# Sheet1.net
KiCad netlist of a schematic drawn in Altium Designer
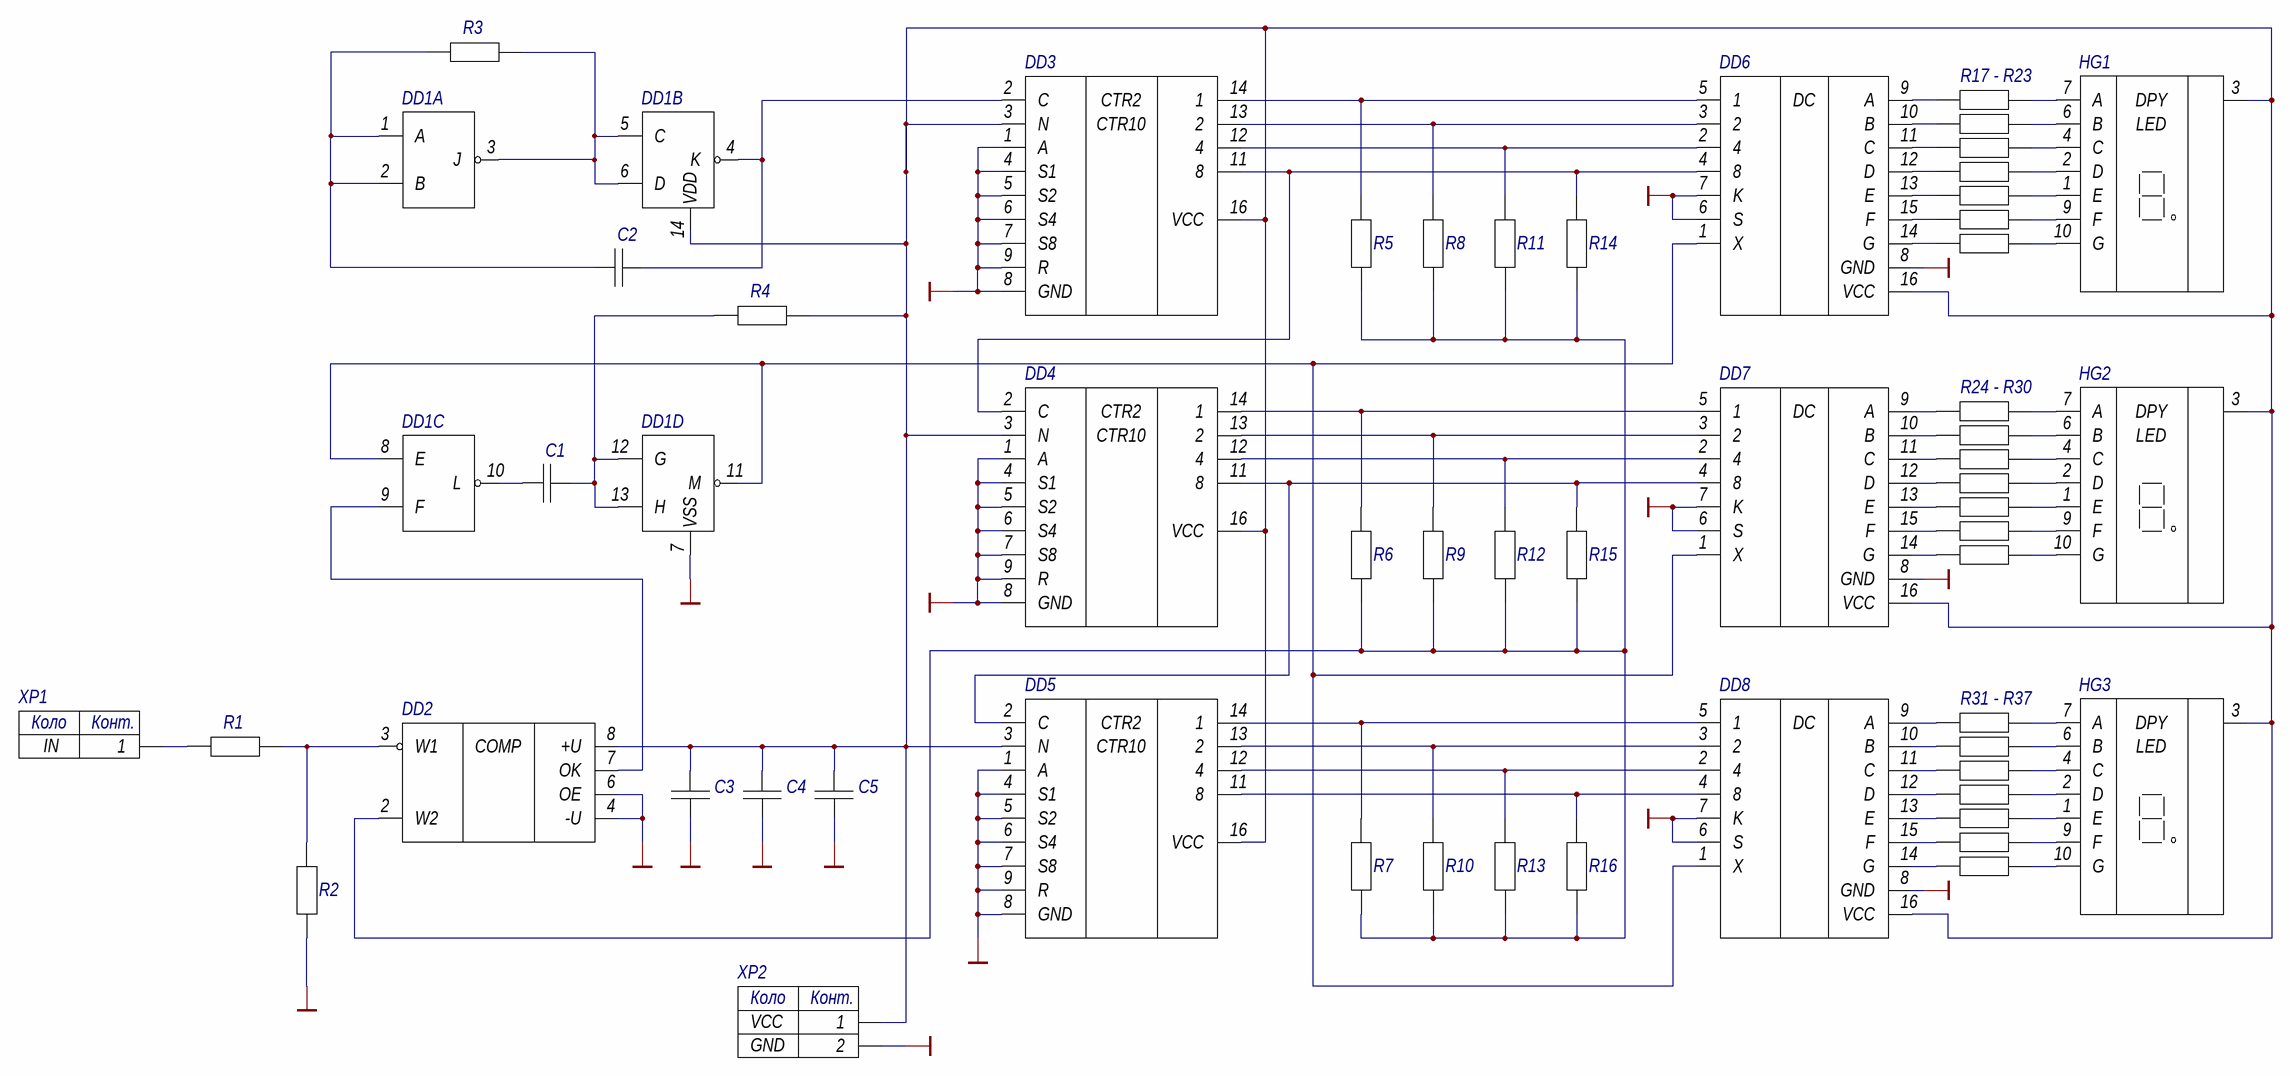
[diagram p0: Sheet1.SchDoc]

(export (version "E")
  (design (tool "Eeschema 10.0.6"))
  (components
    (comp (ref "C1")
      (value "C-0805 50 В 1,2 нФ 10% X7R KEMET")
      (footprint "CAPC2012X09N")
      (description "CAP CER 1200PF 50V X7R 0805")
      (fields (field (name "VOLTAGE") "50 В") (field (name "MANUFACTURER") "KEMET"))
      (libsource (lib "Schlib1") (part "C0805C122K5RAC7800"))
    )
    (comp (ref "C2")
      (value "C-0805 50 В 1,8 нФ 10% X7R KEMET")
      (footprint "CAPC2012X09N")
      (description "CAP CER 1800PF 50V X7R 0805")
      (fields (field (name "VOLTAGE") "50 В") (field (name "MANUFACTURER") "KEMET"))
      (libsource (lib "Schlib1") (part "C0805C182K5RAC7800"))
    )
    (comp (ref "C3")
      (value "C-1210 16 В 100 мкФ 20% X5R KEMET")
      (footprint "CAPC3225X27N")
      (description "CAP CER 100UF 16V X5R 1210")
      (fields (field (name "VOLTAGE") "16 В") (field (name "MANUFACTURER") "KEMET"))
      (libsource (lib "Schlib1") (part "C1210C107M4PAC7800"))
    )
    (comp (ref "C4")
      (value "C-1210 16 В 100 мкФ 20% X5R KEMET")
      (footprint "CAPC3225X27N")
      (description "CAP CER 100UF 16V X5R 1210")
      (fields (field (name "VOLTAGE") "16 В") (field (name "MANUFACTURER") "KEMET"))
      (libsource (lib "Schlib1") (part "C1210C107M4PAC7800"))
    )
    (comp (ref "C5")
      (value "C-1210 16 В 100 мкФ 20% X5R KEMET")
      (footprint "CAPC3225X27N")
      (description "CAP CER 100UF 16V X5R 1210")
      (fields (field (name "VOLTAGE") "16 В") (field (name "MANUFACTURER") "KEMET"))
      (libsource (lib "Schlib1") (part "C1210C107M4PAC7800"))
    )
    (comp (ref "DD1")
      (value "CD4001BPWR Texas Instruments")
      (footprint "TSOP65P640X120-14N")
      (description "IC GATE NOR 4CH 2-INP 14TSSOP")
      (fields (field (name "MANUFACTURER") "Texas Instruments"))
      (libsource (lib "Schlib1") (part "CD4001BPWR"))
    )
    (comp (ref "DD2")
      (value "LM311N STMicroelectronics")
      (footprint "DIP-8_STM")
      (description "IC VOLTAGE COMPARATOR 8-DIP")
      (fields (field (name "MANUFACTURER") "STMicroelectronics"))
      (libsource (lib "Schlib1") (part "LM311N"))
    )
    (comp (ref "DD3")
      (value "TC-5971")
      (footprint "TC5971")
      (description "IC COUNTER BINARY/DECADE")
      (libsource (lib "Schlib1") (part "TC-5971"))
    )
    (comp (ref "DD4")
      (value "TC-5971")
      (footprint "TC5971")
      (description "IC COUNTER BINARY/DECADE")
      (libsource (lib "Schlib1") (part "TC-5971"))
    )
    (comp (ref "DD5")
      (value "TC-5971")
      (footprint "TC5971")
      (description "IC COUNTER BINARY/DECADE")
      (libsource (lib "Schlib1") (part "TC-5971"))
    )
    (comp (ref "DD6")
      (value "CD4511BNSR Texas Instruments")
      (footprint "SOIC127P780X200-16N")
      (description "IC DRVR 7 SEGMENT 16SO")
      (fields (field (name "MANUFACTURER") "Texas Instruments"))
      (libsource (lib "Schlib1") (part "CD4511BNSR"))
    )
    (comp (ref "DD7")
      (value "CD4511BNSR Texas Instruments")
      (footprint "SOIC127P780X200-16N")
      (description "IC DRVR 7 SEGMENT 16SO")
      (fields (field (name "MANUFACTURER") "Texas Instruments"))
      (libsource (lib "Schlib1") (part "CD4511BNSR"))
    )
    (comp (ref "DD8")
      (value "CD4511BNSR Texas Instruments")
      (footprint "SOIC127P780X200-16N")
      (description "IC DRVR 7 SEGMENT 16SO")
      (fields (field (name "MANUFACTURER") "Texas Instruments"))
      (libsource (lib "Schlib1") (part "CD4511BNSR"))
    )
    (comp (ref "HG1")
      (value "ACSC56-41QBWA/D-F01 Kingbright")
      (footprint "ACSX56-41")
      (description "DISPLAY 7SEG 0.56\" SGL BLU 10SMD")
      (fields (field (name "MANUFACTURER") "Kingbright"))
      (libsource (lib "Schlib1") (part "ACSC56-41QBWA/D-F01"))
    )
    (comp (ref "HG2")
      (value "ACSC56-41QBWA/D-F01 Kingbright")
      (footprint "ACSX56-41")
      (description "DISPLAY 7SEG 0.56\" SGL BLU 10SMD")
      (fields (field (name "MANUFACTURER") "Kingbright"))
      (libsource (lib "Schlib1") (part "ACSC56-41QBWA/D-F01"))
    )
    (comp (ref "HG3")
      (value "ACSC56-41QBWA/D-F01 Kingbright")
      (footprint "ACSX56-41")
      (description "DISPLAY 7SEG 0.56\" SGL BLU 10SMD")
      (fields (field (name "MANUFACTURER") "Kingbright"))
      (libsource (lib "Schlib1") (part "ACSC56-41QBWA/D-F01"))
    )
    (comp (ref "R1")
      (value "R-0805 0,125 Вт 10 кОм 5% YAGEO")
      (footprint "RESC2012X05N")
      (description "RES 10K OHM 5% 1/8W 0805")
      (fields (field (name "POWER") "0,125 Вт") (field (name "TOLERANCE") "5%"))
      (libsource (lib "Schlib1") (part "RC0805JR-0710KL"))
    )
    (comp (ref "R2")
      (value "R-0805 0,125 Вт 100 кОм 5% YAGEO")
      (footprint "RESC2012X05N")
      (description "RES 100K OHM 5% 1/8W 0805")
      (fields (field (name "POWER") "0,125 Вт") (field (name "TOLERANCE") "5%"))
      (libsource (lib "Schlib1") (part "RC0805JR-07100KL"))
    )
    (comp (ref "R3")
      (value "R-0805 0,125 Вт 360 кОм 5% YAGEO")
      (footprint "RESC2012X05N")
      (description "RES 360K OHM 5% 1/8W 0805")
      (fields (field (name "POWER") "0,125 Вт") (field (name "TOLERANCE") "5%"))
      (libsource (lib "Schlib1") (part "RC0805JR-07360KL"))
    )
    (comp (ref "R4")
      (value "R-0805 0,125 Вт 360 кОм 5% YAGEO")
      (footprint "RESC2012X05N")
      (description "RES 360K OHM 5% 1/8W 0805")
      (fields (field (name "POWER") "0,125 Вт") (field (name "TOLERANCE") "5%"))
      (libsource (lib "Schlib1") (part "RC0805JR-07360KL"))
    )
    (comp (ref "R5")
      (value "R-0805 0,125 Вт 36 кОм 5% YAGEO")
      (footprint "RESC2012X05N")
      (description "RES 36K OHM 5% 1/8W 0805")
      (fields (field (name "POWER") "0,125 Вт") (field (name "TOLERANCE") "5%"))
      (libsource (lib "Schlib1") (part "RC0805JR-0736KL"))
    )
    (comp (ref "R6")
      (value "R-0805 0,125 Вт 360 кОм 5% YAGEO")
      (footprint "RESC2012X05N")
      (description "RES 360K OHM 5% 1/8W 0805")
      (fields (field (name "POWER") "0,125 Вт") (field (name "TOLERANCE") "5%"))
      (libsource (lib "Schlib1") (part "RC0805JR-07360KL"))
    )
    (comp (ref "R7")
      (value "R-0805 0,125 Вт 3,6 МОм 5% YAGEO")
      (footprint "RESC2012X05N")
      (description "RES 3.6M OHM 5% 1/8W 0805")
      (fields (field (name "POWER") "0,125 Вт") (field (name "TOLERANCE") "5%"))
      (libsource (lib "Schlib1") (part "RC0805JR-073M6L"))
    )
    (comp (ref "R8")
      (value "R-0805 0,125 Вт 18 кОм 5% YAGEO")
      (footprint "RESC2012X05N")
      (description "RES 18K OHM 5% 1/8W 0805")
      (fields (field (name "POWER") "0,125 Вт") (field (name "TOLERANCE") "5%"))
      (libsource (lib "Schlib1") (part "RC0805JR-0718KL"))
    )
    (comp (ref "R9")
      (value "R-0805 0,125 Вт 180 кОм 5% YAGEO")
      (footprint "RESC2012X05N")
      (description "RES 180K OHM 5% 1/8W 0805")
      (fields (field (name "POWER") "0,125 Вт") (field (name "TOLERANCE") "5%"))
      (libsource (lib "Schlib1") (part "RC0805JR-07180KL"))
    )
    (comp (ref "R10")
      (value "R-0805 0,125 Вт 1,8 МОм 5% YAGEO")
      (footprint "RESC2012X05N")
      (description "RES 1.8M OHM 5% 1/8W 0805")
      (fields (field (name "POWER") "0,125 Вт") (field (name "TOLERANCE") "5%"))
      (libsource (lib "Schlib1") (part "RC0805JR-071M8L"))
    )
    (comp (ref "R11")
      (value "R-0805 0,125 Вт 9,1 кОм 5% YAGEO")
      (footprint "RESC2012X05N")
      (description "RES 9.1K OHM 5% 1/8W 0805")
      (fields (field (name "POWER") "0,125 Вт") (field (name "TOLERANCE") "5%"))
      (libsource (lib "Schlib1") (part "RC0805JR-079K1L"))
    )
    (comp (ref "R12")
      (value "R-0805 0,125 Вт 91 кОм 5% YAGEO")
      (footprint "RESC2012X05N")
      (description "RES 91K OHM 5% 1/8W 0805")
      (fields (field (name "POWER") "0,125 Вт") (field (name "TOLERANCE") "5%"))
      (libsource (lib "Schlib1") (part "RC0805JR-0791KL"))
    )
    (comp (ref "R13")
      (value "R-0805 0,125 Вт 910 кОм 5% YAGEO")
      (footprint "RESC2012X05N")
      (description "RES 910K OHM 5% 1/8W 0805")
      (fields (field (name "POWER") "0,125 Вт") (field (name "TOLERANCE") "5%"))
      (libsource (lib "Schlib1") (part "RC0805JR-07910KL"))
    )
    (comp (ref "R14")
      (value "R-0805 0,125 Вт 4,7 кОм 5% YAGEO")
      (footprint "RESC2012X05N")
      (description "RES 4.7K OHM 5% 1/8W 0805")
      (fields (field (name "POWER") "0,125 Вт") (field (name "TOLERANCE") "5%"))
      (libsource (lib "Schlib1") (part "RC0805JR-074K7L"))
    )
    (comp (ref "R15")
      (value "R-0805 0,125 Вт 47 кОм 5% YAGEO")
      (footprint "RESC2012X05N")
      (description "RES 47K OHM 5% 1/8W 0805")
      (fields (field (name "POWER") "0,125 Вт") (field (name "TOLERANCE") "5%"))
      (libsource (lib "Schlib1") (part "RC0805JR-0747KL"))
    )
    (comp (ref "R16")
      (value "R-0805 0,125 Вт 470 кОм 5% YAGEO")
      (footprint "RESC2012X05N")
      (description "RES 470K OHM 5% 1/8W 0805")
      (fields (field (name "POWER") "0,125 Вт") (field (name "TOLERANCE") "5%"))
      (libsource (lib "Schlib1") (part "RC0805JR-07470KL"))
    )
    (comp (ref "R17")
      (value "R-0805 0,125 Вт 470 кОм 5% YAGEO")
      (footprint "RESC2012X05N")
      (description "RES 470K OHM 5% 1/8W 0805")
      (fields (field (name "POWER") "0,125 Вт") (field (name "TOLERANCE") "5%"))
      (libsource (lib "Schlib1") (part "RC0805JR-07470KL"))
    )
    (comp (ref "R18")
      (value "R-0805 0,125 Вт 470 кОм 5% YAGEO")
      (footprint "RESC2012X05N")
      (description "RES 470K OHM 5% 1/8W 0805")
      (fields (field (name "POWER") "0,125 Вт") (field (name "TOLERANCE") "5%"))
      (libsource (lib "Schlib1") (part "RC0805JR-07470KL"))
    )
    (comp (ref "R19")
      (value "R-0805 0,125 Вт 470 кОм 5% YAGEO")
      (footprint "RESC2012X05N")
      (description "RES 470K OHM 5% 1/8W 0805")
      (fields (field (name "POWER") "0,125 Вт") (field (name "TOLERANCE") "5%"))
      (libsource (lib "Schlib1") (part "RC0805JR-07470KL"))
    )
    (comp (ref "R20")
      (value "R-0805 0,125 Вт 470 кОм 5% YAGEO")
      (footprint "RESC2012X05N")
      (description "RES 470K OHM 5% 1/8W 0805")
      (fields (field (name "POWER") "0,125 Вт") (field (name "TOLERANCE") "5%"))
      (libsource (lib "Schlib1") (part "RC0805JR-07470KL"))
    )
    (comp (ref "R21")
      (value "R-0805 0,125 Вт 470 кОм 5% YAGEO")
      (footprint "RESC2012X05N")
      (description "RES 470K OHM 5% 1/8W 0805")
      (fields (field (name "POWER") "0,125 Вт") (field (name "TOLERANCE") "5%"))
      (libsource (lib "Schlib1") (part "RC0805JR-07470KL"))
    )
    (comp (ref "R22")
      (value "R-0805 0,125 Вт 470 кОм 5% YAGEO")
      (footprint "RESC2012X05N")
      (description "RES 470K OHM 5% 1/8W 0805")
      (fields (field (name "POWER") "0,125 Вт") (field (name "TOLERANCE") "5%"))
      (libsource (lib "Schlib1") (part "RC0805JR-07470KL"))
    )
    (comp (ref "R23")
      (value "R-0805 0,125 Вт 470 кОм 5% YAGEO")
      (footprint "RESC2012X05N")
      (description "RES 470K OHM 5% 1/8W 0805")
      (fields (field (name "POWER") "0,125 Вт") (field (name "TOLERANCE") "5%"))
      (libsource (lib "Schlib1") (part "RC0805JR-07470KL"))
    )
    (comp (ref "R24")
      (value "R-0805 0,125 Вт 470 кОм 5% YAGEO")
      (footprint "RESC2012X05N")
      (description "RES 470K OHM 5% 1/8W 0805")
      (fields (field (name "POWER") "0,125 Вт") (field (name "TOLERANCE") "5%"))
      (libsource (lib "Schlib1") (part "RC0805JR-07470KL"))
    )
    (comp (ref "R25")
      (value "R-0805 0,125 Вт 470 кОм 5% YAGEO")
      (footprint "RESC2012X05N")
      (description "RES 470K OHM 5% 1/8W 0805")
      (fields (field (name "POWER") "0,125 Вт") (field (name "TOLERANCE") "5%"))
      (libsource (lib "Schlib1") (part "RC0805JR-07470KL"))
    )
    (comp (ref "R26")
      (value "R-0805 0,125 Вт 470 кОм 5% YAGEO")
      (footprint "RESC2012X05N")
      (description "RES 470K OHM 5% 1/8W 0805")
      (fields (field (name "POWER") "0,125 Вт") (field (name "TOLERANCE") "5%"))
      (libsource (lib "Schlib1") (part "RC0805JR-07470KL"))
    )
    (comp (ref "R27")
      (value "R-0805 0,125 Вт 470 кОм 5% YAGEO")
      (footprint "RESC2012X05N")
      (description "RES 470K OHM 5% 1/8W 0805")
      (fields (field (name "POWER") "0,125 Вт") (field (name "TOLERANCE") "5%"))
      (libsource (lib "Schlib1") (part "RC0805JR-07470KL"))
    )
    (comp (ref "R28")
      (value "R-0805 0,125 Вт 470 кОм 5% YAGEO")
      (footprint "RESC2012X05N")
      (description "RES 470K OHM 5% 1/8W 0805")
      (fields (field (name "POWER") "0,125 Вт") (field (name "TOLERANCE") "5%"))
      (libsource (lib "Schlib1") (part "RC0805JR-07470KL"))
    )
    (comp (ref "R29")
      (value "R-0805 0,125 Вт 470 кОм 5% YAGEO")
      (footprint "RESC2012X05N")
      (description "RES 470K OHM 5% 1/8W 0805")
      (fields (field (name "POWER") "0,125 Вт") (field (name "TOLERANCE") "5%"))
      (libsource (lib "Schlib1") (part "RC0805JR-07470KL"))
    )
    (comp (ref "R30")
      (value "R-0805 0,125 Вт 470 кОм 5% YAGEO")
      (footprint "RESC2012X05N")
      (description "RES 470K OHM 5% 1/8W 0805")
      (fields (field (name "POWER") "0,125 Вт") (field (name "TOLERANCE") "5%"))
      (libsource (lib "Schlib1") (part "RC0805JR-07470KL"))
    )
    (comp (ref "R31")
      (value "R-0805 0,125 Вт 470 кОм 5% YAGEO")
      (footprint "RESC2012X05N")
      (description "RES 470K OHM 5% 1/8W 0805")
      (fields (field (name "POWER") "0,125 Вт") (field (name "TOLERANCE") "5%"))
      (libsource (lib "Schlib1") (part "RC0805JR-07470KL"))
    )
    (comp (ref "R32")
      (value "R-0805 0,125 Вт 470 кОм 5% YAGEO")
      (footprint "RESC2012X05N")
      (description "RES 470K OHM 5% 1/8W 0805")
      (fields (field (name "POWER") "0,125 Вт") (field (name "TOLERANCE") "5%"))
      (libsource (lib "Schlib1") (part "RC0805JR-07470KL"))
    )
    (comp (ref "R33")
      (value "R-0805 0,125 Вт 470 кОм 5% YAGEO")
      (footprint "RESC2012X05N")
      (description "RES 470K OHM 5% 1/8W 0805")
      (fields (field (name "POWER") "0,125 Вт") (field (name "TOLERANCE") "5%"))
      (libsource (lib "Schlib1") (part "RC0805JR-07470KL"))
    )
    (comp (ref "R34")
      (value "R-0805 0,125 Вт 470 кОм 5% YAGEO")
      (footprint "RESC2012X05N")
      (description "RES 470K OHM 5% 1/8W 0805")
      (fields (field (name "POWER") "0,125 Вт") (field (name "TOLERANCE") "5%"))
      (libsource (lib "Schlib1") (part "RC0805JR-07470KL"))
    )
    (comp (ref "R35")
      (value "R-0805 0,125 Вт 470 кОм 5% YAGEO")
      (footprint "RESC2012X05N")
      (description "RES 470K OHM 5% 1/8W 0805")
      (fields (field (name "POWER") "0,125 Вт") (field (name "TOLERANCE") "5%"))
      (libsource (lib "Schlib1") (part "RC0805JR-07470KL"))
    )
    (comp (ref "R36")
      (value "R-0805 0,125 Вт 470 кОм 5% YAGEO")
      (footprint "RESC2012X05N")
      (description "RES 470K OHM 5% 1/8W 0805")
      (fields (field (name "POWER") "0,125 Вт") (field (name "TOLERANCE") "5%"))
      (libsource (lib "Schlib1") (part "RC0805JR-07470KL"))
    )
    (comp (ref "R37")
      (value "R-0805 0,125 Вт 470 кОм 5% YAGEO")
      (footprint "RESC2012X05N")
      (description "RES 470K OHM 5% 1/8W 0805")
      (fields (field (name "POWER") "0,125 Вт") (field (name "TOLERANCE") "5%"))
      (libsource (lib "Schlib1") (part "RC0805JR-07470KL"))
    )
    (comp (ref "XP1")
      (value "61300111121 Würth Elektronik")
      (footprint "PLS-1")
      (description "CONN HEADER VERT 1POS")
      (fields (field (name "MANUFACTURER") "Würth Elektronik"))
      (libsource (lib "Schlib1") (part "61300111121"))
    )
    (comp (ref "XP2")
      (value "61300211121 Würth Elektronik")
      (footprint "PLS-2")
      (description "CONN HEADER VERT 2POS 2.54MM")
      (fields (field (name "MANUFACTURER") "Würth Elektronik"))
      (libsource (lib "Schlib1") (part "61300211121"))
    )
  )
  (nets
    (net (code "1") (name "GND") (class "Default")
      (node (ref "C3") (pin "1") (pinfunction "1_1") (pintype "passive"))
      (node (ref "C4") (pin "1") (pinfunction "1_1") (pintype "passive"))
      (node (ref "C5") (pin "1") (pinfunction "1_1") (pintype "passive"))
      (node (ref "DD1") (pin "7") (pinfunction "VSS_7") (pintype "passive"))
      (node (ref "DD2") (pin "4") (pinfunction "-U_4") (pintype "passive"))
      (node (ref "DD2") (pin "6") (pinfunction "OE_6") (pintype "passive"))
      (node (ref "DD3") (pin "1") (pinfunction "A_1") (pintype "passive"))
      (node (ref "DD3") (pin "4") (pinfunction "S1_4") (pintype "passive"))
      (node (ref "DD3") (pin "5") (pinfunction "S2_5") (pintype "passive"))
      (node (ref "DD3") (pin "6") (pinfunction "S4_6") (pintype "passive"))
      (node (ref "DD3") (pin "7") (pinfunction "S8_7") (pintype "passive"))
      (node (ref "DD3") (pin "8") (pinfunction "GND_8") (pintype "passive"))
      (node (ref "DD3") (pin "9") (pinfunction "R_9") (pintype "passive"))
      (node (ref "DD4") (pin "1") (pinfunction "A_1") (pintype "passive"))
      (node (ref "DD4") (pin "4") (pinfunction "S1_4") (pintype "passive"))
      (node (ref "DD4") (pin "5") (pinfunction "S2_5") (pintype "passive"))
      (node (ref "DD4") (pin "6") (pinfunction "S4_6") (pintype "passive"))
      (node (ref "DD4") (pin "7") (pinfunction "S8_7") (pintype "passive"))
      (node (ref "DD4") (pin "8") (pinfunction "GND_8") (pintype "passive"))
      (node (ref "DD4") (pin "9") (pinfunction "R_9") (pintype "passive"))
      (node (ref "DD5") (pin "1") (pinfunction "A_1") (pintype "passive"))
      (node (ref "DD5") (pin "4") (pinfunction "S1_4") (pintype "passive"))
      (node (ref "DD5") (pin "5") (pinfunction "S2_5") (pintype "passive"))
      (node (ref "DD5") (pin "6") (pinfunction "S4_6") (pintype "passive"))
      (node (ref "DD5") (pin "7") (pinfunction "S8_7") (pintype "passive"))
      (node (ref "DD5") (pin "8") (pinfunction "GND_8") (pintype "passive"))
      (node (ref "DD5") (pin "9") (pinfunction "R_9") (pintype "passive"))
      (node (ref "DD6") (pin "6") (pinfunction "S_6") (pintype "passive"))
      (node (ref "DD6") (pin "7") (pinfunction "K_7") (pintype "passive"))
      (node (ref "DD6") (pin "8") (pinfunction "GND_8") (pintype "passive"))
      (node (ref "DD7") (pin "6") (pinfunction "S_6") (pintype "passive"))
      (node (ref "DD7") (pin "7") (pinfunction "K_7") (pintype "passive"))
      (node (ref "DD7") (pin "8") (pinfunction "GND_8") (pintype "passive"))
      (node (ref "DD8") (pin "6") (pinfunction "S_6") (pintype "passive"))
      (node (ref "DD8") (pin "7") (pinfunction "K_7") (pintype "passive"))
      (node (ref "DD8") (pin "8") (pinfunction "GND_8") (pintype "passive"))
      (node (ref "R2") (pin "1") (pinfunction "1_1") (pintype "passive"))
      (node (ref "XP2") (pin "2") (pinfunction "2_2") (pintype "passive"))
    )
    (net (code "2") (name "Net-(DD1A-A)") (class "Default")
      (node (ref "C2") (pin "1") (pinfunction "1_1") (pintype "passive"))
      (node (ref "DD1") (pin "1") (pinfunction "A_1") (pintype "passive"))
      (node (ref "DD1") (pin "2") (pinfunction "B_2") (pintype "passive"))
      (node (ref "R3") (pin "1") (pinfunction "1_1") (pintype "passive"))
    )
    (net (code "3") (name "Net-(DD1A-J)") (class "Default")
      (node (ref "DD1") (pin "3") (pinfunction "J_3") (pintype "passive"))
      (node (ref "DD1") (pin "5") (pinfunction "C_5") (pintype "passive"))
      (node (ref "DD1") (pin "6") (pinfunction "D_6") (pintype "passive"))
      (node (ref "R3") (pin "2") (pinfunction "2_2") (pintype "passive"))
    )
    (net (code "4") (name "Net-(DD1B-K)") (class "Default")
      (node (ref "C2") (pin "2") (pinfunction "2_2") (pintype "passive"))
      (node (ref "DD1") (pin "4") (pinfunction "K_4") (pintype "passive"))
      (node (ref "DD3") (pin "2") (pinfunction "C_2") (pintype "passive"))
    )
    (net (code "5") (name "Net-(DD1B-VDD)") (class "Default")
      (node (ref "C3") (pin "2") (pinfunction "2_2") (pintype "passive"))
      (node (ref "C4") (pin "2") (pinfunction "2_2") (pintype "passive"))
      (node (ref "C5") (pin "2") (pinfunction "2_2") (pintype "passive"))
      (node (ref "DD1") (pin "14") (pinfunction "VDD_14") (pintype "passive"))
      (node (ref "DD2") (pin "8") (pinfunction "+U_8") (pintype "passive"))
      (node (ref "DD3") (pin "16") (pinfunction "VCC_16") (pintype "passive"))
      (node (ref "DD3") (pin "3") (pinfunction "N_3") (pintype "passive"))
      (node (ref "DD4") (pin "16") (pinfunction "VCC_16") (pintype "passive"))
      (node (ref "DD4") (pin "3") (pinfunction "N_3") (pintype "passive"))
      (node (ref "DD5") (pin "16") (pinfunction "VCC_16") (pintype "passive"))
      (node (ref "DD5") (pin "3") (pinfunction "N_3") (pintype "passive"))
      (node (ref "DD6") (pin "16") (pinfunction "VCC_16") (pintype "passive"))
      (node (ref "DD7") (pin "16") (pinfunction "VCC_16") (pintype "passive"))
      (node (ref "DD8") (pin "16") (pinfunction "VCC_16") (pintype "passive"))
      (node (ref "HG1") (pin "3") (pinfunction "3_3") (pintype "passive"))
      (node (ref "HG2") (pin "3") (pinfunction "3_3") (pintype "passive"))
      (node (ref "HG3") (pin "3") (pinfunction "3_3") (pintype "passive"))
      (node (ref "R4") (pin "2") (pinfunction "2_2") (pintype "passive"))
      (node (ref "XP2") (pin "1") (pinfunction "1_1") (pintype "passive"))
    )
    (net (code "6") (name "Net-(DD1C-E)") (class "Default")
      (node (ref "DD1") (pin "11") (pinfunction "M_11") (pintype "passive"))
      (node (ref "DD1") (pin "8") (pinfunction "E_8") (pintype "passive"))
      (node (ref "DD6") (pin "1") (pinfunction "X_1") (pintype "passive"))
      (node (ref "DD7") (pin "1") (pinfunction "X_1") (pintype "passive"))
      (node (ref "DD8") (pin "1") (pinfunction "X_1") (pintype "passive"))
    )
    (net (code "7") (name "Net-(DD1C-F)") (class "Default")
      (node (ref "DD1") (pin "9") (pinfunction "F_9") (pintype "passive"))
      (node (ref "DD2") (pin "7") (pinfunction "OK_7") (pintype "passive"))
    )
    (net (code "8") (name "Net-(DD1C-L)") (class "Default")
      (node (ref "C1") (pin "1") (pinfunction "1_1") (pintype "passive"))
      (node (ref "DD1") (pin "10") (pinfunction "L_10") (pintype "passive"))
    )
    (net (code "9") (name "Net-(DD1D-G)") (class "Default")
      (node (ref "C1") (pin "2") (pinfunction "2_2") (pintype "passive"))
      (node (ref "DD1") (pin "12") (pinfunction "G_12") (pintype "passive"))
      (node (ref "DD1") (pin "13") (pinfunction "H_13") (pintype "passive"))
      (node (ref "R4") (pin "1") (pinfunction "1_1") (pintype "passive"))
    )
    (net (code "10") (name "Net-(DD2-W1)") (class "Default")
      (node (ref "DD2") (pin "3") (pinfunction "W1_3") (pintype "passive"))
      (node (ref "R1") (pin "2") (pinfunction "2_2") (pintype "passive"))
      (node (ref "R2") (pin "2") (pinfunction "2_2") (pintype "passive"))
    )
    (net (code "11") (name "Net-(DD2-W2)") (class "Default")
      (node (ref "DD2") (pin "2") (pinfunction "W2_2") (pintype "passive"))
      (node (ref "R10") (pin "1") (pinfunction "1_1") (pintype "passive"))
      (node (ref "R11") (pin "1") (pinfunction "1_1") (pintype "passive"))
      (node (ref "R12") (pin "1") (pinfunction "1_1") (pintype "passive"))
      (node (ref "R13") (pin "1") (pinfunction "1_1") (pintype "passive"))
      (node (ref "R14") (pin "1") (pinfunction "1_1") (pintype "passive"))
      (node (ref "R15") (pin "1") (pinfunction "1_1") (pintype "passive"))
      (node (ref "R16") (pin "1") (pinfunction "1_1") (pintype "passive"))
      (node (ref "R5") (pin "1") (pinfunction "1_1") (pintype "passive"))
      (node (ref "R6") (pin "1") (pinfunction "1_1") (pintype "passive"))
      (node (ref "R7") (pin "1") (pinfunction "1_1") (pintype "passive"))
      (node (ref "R8") (pin "1") (pinfunction "1_1") (pintype "passive"))
      (node (ref "R9") (pin "1") (pinfunction "1_1") (pintype "passive"))
    )
    (net (code "12") (name "Net-(DD3-1)") (class "Default")
      (node (ref "DD3") (pin "14") (pinfunction "1_14") (pintype "passive"))
      (node (ref "DD6") (pin "5") (pinfunction "1_5") (pintype "passive"))
      (node (ref "R5") (pin "2") (pinfunction "2_2") (pintype "passive"))
    )
    (net (code "13") (name "Net-(DD3-2)") (class "Default")
      (node (ref "DD3") (pin "13") (pinfunction "2_13") (pintype "passive"))
      (node (ref "DD6") (pin "3") (pinfunction "2_3") (pintype "passive"))
      (node (ref "R8") (pin "2") (pinfunction "2_2") (pintype "passive"))
    )
    (net (code "14") (name "Net-(DD3-4)") (class "Default")
      (node (ref "DD3") (pin "12") (pinfunction "4_12") (pintype "passive"))
      (node (ref "DD6") (pin "2") (pinfunction "4_2") (pintype "passive"))
      (node (ref "R11") (pin "2") (pinfunction "2_2") (pintype "passive"))
    )
    (net (code "15") (name "Net-(DD3-8)") (class "Default")
      (node (ref "DD3") (pin "11") (pinfunction "8_11") (pintype "passive"))
      (node (ref "DD4") (pin "2") (pinfunction "C_2") (pintype "passive"))
      (node (ref "DD6") (pin "4") (pinfunction "8_4") (pintype "passive"))
      (node (ref "R14") (pin "2") (pinfunction "2_2") (pintype "passive"))
    )
    (net (code "16") (name "Net-(DD4-1)") (class "Default")
      (node (ref "DD4") (pin "14") (pinfunction "1_14") (pintype "passive"))
      (node (ref "DD7") (pin "5") (pinfunction "1_5") (pintype "passive"))
      (node (ref "R6") (pin "2") (pinfunction "2_2") (pintype "passive"))
    )
    (net (code "17") (name "Net-(DD4-2)") (class "Default")
      (node (ref "DD4") (pin "13") (pinfunction "2_13") (pintype "passive"))
      (node (ref "DD7") (pin "3") (pinfunction "2_3") (pintype "passive"))
      (node (ref "R9") (pin "2") (pinfunction "2_2") (pintype "passive"))
    )
    (net (code "18") (name "Net-(DD4-4)") (class "Default")
      (node (ref "DD4") (pin "12") (pinfunction "4_12") (pintype "passive"))
      (node (ref "DD7") (pin "2") (pinfunction "4_2") (pintype "passive"))
      (node (ref "R12") (pin "2") (pinfunction "2_2") (pintype "passive"))
    )
    (net (code "19") (name "Net-(DD4-8)") (class "Default")
      (node (ref "DD4") (pin "11") (pinfunction "8_11") (pintype "passive"))
      (node (ref "DD5") (pin "2") (pinfunction "C_2") (pintype "passive"))
      (node (ref "DD7") (pin "4") (pinfunction "8_4") (pintype "passive"))
      (node (ref "R15") (pin "2") (pinfunction "2_2") (pintype "passive"))
    )
    (net (code "20") (name "Net-(DD5-1)") (class "Default")
      (node (ref "DD5") (pin "14") (pinfunction "1_14") (pintype "passive"))
      (node (ref "DD8") (pin "5") (pinfunction "1_5") (pintype "passive"))
      (node (ref "R7") (pin "2") (pinfunction "2_2") (pintype "passive"))
    )
    (net (code "21") (name "Net-(DD5-2)") (class "Default")
      (node (ref "DD5") (pin "13") (pinfunction "2_13") (pintype "passive"))
      (node (ref "DD8") (pin "3") (pinfunction "2_3") (pintype "passive"))
      (node (ref "R10") (pin "2") (pinfunction "2_2") (pintype "passive"))
    )
    (net (code "22") (name "Net-(DD5-4)") (class "Default")
      (node (ref "DD5") (pin "12") (pinfunction "4_12") (pintype "passive"))
      (node (ref "DD8") (pin "2") (pinfunction "4_2") (pintype "passive"))
      (node (ref "R13") (pin "2") (pinfunction "2_2") (pintype "passive"))
    )
    (net (code "23") (name "Net-(DD5-8)") (class "Default")
      (node (ref "DD5") (pin "11") (pinfunction "8_11") (pintype "passive"))
      (node (ref "DD8") (pin "4") (pinfunction "8_4") (pintype "passive"))
      (node (ref "R16") (pin "2") (pinfunction "2_2") (pintype "passive"))
    )
    (net (code "24") (name "Net-(DD6-A)") (class "Default")
      (node (ref "DD6") (pin "9") (pinfunction "A_9") (pintype "passive"))
      (node (ref "R17") (pin "1") (pinfunction "1_1") (pintype "passive"))
    )
    (net (code "25") (name "Net-(DD6-B)") (class "Default")
      (node (ref "DD6") (pin "10") (pinfunction "B_10") (pintype "passive"))
      (node (ref "R18") (pin "1") (pinfunction "1_1") (pintype "passive"))
    )
    (net (code "26") (name "Net-(DD6-C)") (class "Default")
      (node (ref "DD6") (pin "11") (pinfunction "C_11") (pintype "passive"))
      (node (ref "R19") (pin "1") (pinfunction "1_1") (pintype "passive"))
    )
    (net (code "27") (name "Net-(DD6-D)") (class "Default")
      (node (ref "DD6") (pin "12") (pinfunction "D_12") (pintype "passive"))
      (node (ref "R20") (pin "1") (pinfunction "1_1") (pintype "passive"))
    )
    (net (code "28") (name "Net-(DD6-E)") (class "Default")
      (node (ref "DD6") (pin "13") (pinfunction "E_13") (pintype "passive"))
      (node (ref "R21") (pin "1") (pinfunction "1_1") (pintype "passive"))
    )
    (net (code "29") (name "Net-(DD6-F)") (class "Default")
      (node (ref "DD6") (pin "15") (pinfunction "F_15") (pintype "passive"))
      (node (ref "R22") (pin "1") (pinfunction "1_1") (pintype "passive"))
    )
    (net (code "30") (name "Net-(DD6-G)") (class "Default")
      (node (ref "DD6") (pin "14") (pinfunction "G_14") (pintype "passive"))
      (node (ref "R23") (pin "1") (pinfunction "1_1") (pintype "passive"))
    )
    (net (code "31") (name "Net-(DD7-A)") (class "Default")
      (node (ref "DD7") (pin "9") (pinfunction "A_9") (pintype "passive"))
      (node (ref "R24") (pin "1") (pinfunction "1_1") (pintype "passive"))
    )
    (net (code "32") (name "Net-(DD7-B)") (class "Default")
      (node (ref "DD7") (pin "10") (pinfunction "B_10") (pintype "passive"))
      (node (ref "R25") (pin "1") (pinfunction "1_1") (pintype "passive"))
    )
    (net (code "33") (name "Net-(DD7-C)") (class "Default")
      (node (ref "DD7") (pin "11") (pinfunction "C_11") (pintype "passive"))
      (node (ref "R26") (pin "1") (pinfunction "1_1") (pintype "passive"))
    )
    (net (code "34") (name "Net-(DD7-D)") (class "Default")
      (node (ref "DD7") (pin "12") (pinfunction "D_12") (pintype "passive"))
      (node (ref "R27") (pin "1") (pinfunction "1_1") (pintype "passive"))
    )
    (net (code "35") (name "Net-(DD7-E)") (class "Default")
      (node (ref "DD7") (pin "13") (pinfunction "E_13") (pintype "passive"))
      (node (ref "R28") (pin "1") (pinfunction "1_1") (pintype "passive"))
    )
    (net (code "36") (name "Net-(DD7-F)") (class "Default")
      (node (ref "DD7") (pin "15") (pinfunction "F_15") (pintype "passive"))
      (node (ref "R29") (pin "1") (pinfunction "1_1") (pintype "passive"))
    )
    (net (code "37") (name "Net-(DD7-G)") (class "Default")
      (node (ref "DD7") (pin "14") (pinfunction "G_14") (pintype "passive"))
      (node (ref "R30") (pin "1") (pinfunction "1_1") (pintype "passive"))
    )
    (net (code "38") (name "Net-(DD8-A)") (class "Default")
      (node (ref "DD8") (pin "9") (pinfunction "A_9") (pintype "passive"))
      (node (ref "R31") (pin "1") (pinfunction "1_1") (pintype "passive"))
    )
    (net (code "39") (name "Net-(DD8-B)") (class "Default")
      (node (ref "DD8") (pin "10") (pinfunction "B_10") (pintype "passive"))
      (node (ref "R32") (pin "1") (pinfunction "1_1") (pintype "passive"))
    )
    (net (code "40") (name "Net-(DD8-C)") (class "Default")
      (node (ref "DD8") (pin "11") (pinfunction "C_11") (pintype "passive"))
      (node (ref "R33") (pin "1") (pinfunction "1_1") (pintype "passive"))
    )
    (net (code "41") (name "Net-(DD8-D)") (class "Default")
      (node (ref "DD8") (pin "12") (pinfunction "D_12") (pintype "passive"))
      (node (ref "R34") (pin "1") (pinfunction "1_1") (pintype "passive"))
    )
    (net (code "42") (name "Net-(DD8-E)") (class "Default")
      (node (ref "DD8") (pin "13") (pinfunction "E_13") (pintype "passive"))
      (node (ref "R35") (pin "1") (pinfunction "1_1") (pintype "passive"))
    )
    (net (code "43") (name "Net-(DD8-F)") (class "Default")
      (node (ref "DD8") (pin "15") (pinfunction "F_15") (pintype "passive"))
      (node (ref "R36") (pin "1") (pinfunction "1_1") (pintype "passive"))
    )
    (net (code "44") (name "Net-(DD8-G)") (class "Default")
      (node (ref "DD8") (pin "14") (pinfunction "G_14") (pintype "passive"))
      (node (ref "R37") (pin "1") (pinfunction "1_1") (pintype "passive"))
    )
    (net (code "45") (name "Net-(HG1-A)") (class "Default")
      (node (ref "HG1") (pin "7") (pinfunction "A_7") (pintype "passive"))
      (node (ref "R17") (pin "2") (pinfunction "2_2") (pintype "passive"))
    )
    (net (code "46") (name "Net-(HG1-B)") (class "Default")
      (node (ref "HG1") (pin "6") (pinfunction "B_6") (pintype "passive"))
      (node (ref "R18") (pin "2") (pinfunction "2_2") (pintype "passive"))
    )
    (net (code "47") (name "Net-(HG1-C)") (class "Default")
      (node (ref "HG1") (pin "4") (pinfunction "C_4") (pintype "passive"))
      (node (ref "R19") (pin "2") (pinfunction "2_2") (pintype "passive"))
    )
    (net (code "48") (name "Net-(HG1-D)") (class "Default")
      (node (ref "HG1") (pin "2") (pinfunction "D_2") (pintype "passive"))
      (node (ref "R20") (pin "2") (pinfunction "2_2") (pintype "passive"))
    )
    (net (code "49") (name "Net-(HG1-E)") (class "Default")
      (node (ref "HG1") (pin "1") (pinfunction "E_1") (pintype "passive"))
      (node (ref "R21") (pin "2") (pinfunction "2_2") (pintype "passive"))
    )
    (net (code "50") (name "Net-(HG1-F)") (class "Default")
      (node (ref "HG1") (pin "9") (pinfunction "F_9") (pintype "passive"))
      (node (ref "R22") (pin "2") (pinfunction "2_2") (pintype "passive"))
    )
    (net (code "51") (name "Net-(HG1-G)") (class "Default")
      (node (ref "HG1") (pin "10") (pinfunction "G_10") (pintype "passive"))
      (node (ref "R23") (pin "2") (pinfunction "2_2") (pintype "passive"))
    )
    (net (code "52") (name "Net-(HG2-A)") (class "Default")
      (node (ref "HG2") (pin "7") (pinfunction "A_7") (pintype "passive"))
      (node (ref "R24") (pin "2") (pinfunction "2_2") (pintype "passive"))
    )
    (net (code "53") (name "Net-(HG2-B)") (class "Default")
      (node (ref "HG2") (pin "6") (pinfunction "B_6") (pintype "passive"))
      (node (ref "R25") (pin "2") (pinfunction "2_2") (pintype "passive"))
    )
    (net (code "54") (name "Net-(HG2-C)") (class "Default")
      (node (ref "HG2") (pin "4") (pinfunction "C_4") (pintype "passive"))
      (node (ref "R26") (pin "2") (pinfunction "2_2") (pintype "passive"))
    )
    (net (code "55") (name "Net-(HG2-D)") (class "Default")
      (node (ref "HG2") (pin "2") (pinfunction "D_2") (pintype "passive"))
      (node (ref "R27") (pin "2") (pinfunction "2_2") (pintype "passive"))
    )
    (net (code "56") (name "Net-(HG2-E)") (class "Default")
      (node (ref "HG2") (pin "1") (pinfunction "E_1") (pintype "passive"))
      (node (ref "R28") (pin "2") (pinfunction "2_2") (pintype "passive"))
    )
    (net (code "57") (name "Net-(HG2-F)") (class "Default")
      (node (ref "HG2") (pin "9") (pinfunction "F_9") (pintype "passive"))
      (node (ref "R29") (pin "2") (pinfunction "2_2") (pintype "passive"))
    )
    (net (code "58") (name "Net-(HG2-G)") (class "Default")
      (node (ref "HG2") (pin "10") (pinfunction "G_10") (pintype "passive"))
      (node (ref "R30") (pin "2") (pinfunction "2_2") (pintype "passive"))
    )
    (net (code "59") (name "Net-(HG3-A)") (class "Default")
      (node (ref "HG3") (pin "7") (pinfunction "A_7") (pintype "passive"))
      (node (ref "R31") (pin "2") (pinfunction "2_2") (pintype "passive"))
    )
    (net (code "60") (name "Net-(HG3-B)") (class "Default")
      (node (ref "HG3") (pin "6") (pinfunction "B_6") (pintype "passive"))
      (node (ref "R32") (pin "2") (pinfunction "2_2") (pintype "passive"))
    )
    (net (code "61") (name "Net-(HG3-C)") (class "Default")
      (node (ref "HG3") (pin "4") (pinfunction "C_4") (pintype "passive"))
      (node (ref "R33") (pin "2") (pinfunction "2_2") (pintype "passive"))
    )
    (net (code "62") (name "Net-(HG3-D)") (class "Default")
      (node (ref "HG3") (pin "2") (pinfunction "D_2") (pintype "passive"))
      (node (ref "R34") (pin "2") (pinfunction "2_2") (pintype "passive"))
    )
    (net (code "63") (name "Net-(HG3-E)") (class "Default")
      (node (ref "HG3") (pin "1") (pinfunction "E_1") (pintype "passive"))
      (node (ref "R35") (pin "2") (pinfunction "2_2") (pintype "passive"))
    )
    (net (code "64") (name "Net-(HG3-F)") (class "Default")
      (node (ref "HG3") (pin "9") (pinfunction "F_9") (pintype "passive"))
      (node (ref "R36") (pin "2") (pinfunction "2_2") (pintype "passive"))
    )
    (net (code "65") (name "Net-(HG3-G)") (class "Default")
      (node (ref "HG3") (pin "10") (pinfunction "G_10") (pintype "passive"))
      (node (ref "R37") (pin "2") (pinfunction "2_2") (pintype "passive"))
    )
    (net (code "66") (name "Net-(R1-Pad1)") (class "Default")
      (node (ref "R1") (pin "1") (pinfunction "1_1") (pintype "passive"))
      (node (ref "XP1") (pin "1") (pinfunction "1_1") (pintype "passive"))
    )
  )
)
